# Barelang-FC_Strategy.net
KiCad netlist of a schematic drawn in Altium Designer
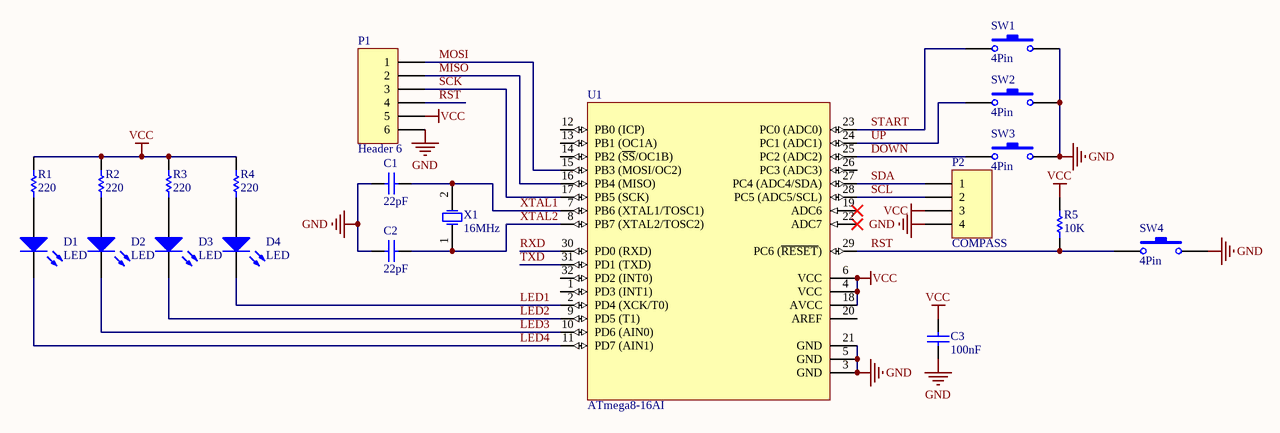
[diagram p0: Barelang-FC Strategy.SchDoc]

(export (version "E")
  (design (tool "Eeschema 10.0.6"))
  (components
    (comp (ref "C1") (value "22pF") (footprint "C0805") (libsource (lib "toko-Embedded") (part "Capacitor")))
    (comp (ref "C2") (value "22pF") (footprint "C0805") (libsource (lib "toko-Embedded") (part "Capacitor")))
    (comp (ref "C3") (value "100nF") (footprint "C0805") (libsource (lib "toko-Embedded") (part "Capacitor")))
    (comp (ref "D1") (value "LED") (footprint "CHIPLED_1206") (libsource (lib "toko-Embedded") (part "LED")))
    (comp (ref "D2") (value "LED") (footprint "CHIPLED_1206") (libsource (lib "toko-Embedded") (part "LED")))
    (comp (ref "D3") (value "LED") (footprint "CHIPLED_1206") (libsource (lib "toko-Embedded") (part "LED")))
    (comp (ref "D4") (value "LED") (footprint "CHIPLED_1206") (libsource (lib "toko-Embedded") (part "LED")))
    (comp (ref "P1")
      (value "Header 6")
      (footprint "HDR1X6")
      (description "Header, 6-Pin")
      (fields (field (name "PUBLISHER") "Altium Limited"))
      (libsource (lib "Miscellaneous Connectors") (part "Header 6"))
    )
    (comp (ref "P2")
      (value "COMPASS")
      (footprint "HDR1X4")
      (description "Header, 4-Pin")
      (fields (field (name "PUBLISHER") "Altium Limited"))
      (libsource (lib "Miscellaneous Connectors") (part "Header 4"))
    )
    (comp (ref "R1") (value "220") (footprint "R0805") (libsource (lib "toko-Embedded") (part "Resistor")))
    (comp (ref "R2") (value "220") (footprint "R0805") (libsource (lib "toko-Embedded") (part "Resistor")))
    (comp (ref "R3") (value "220") (footprint "R0805") (libsource (lib "toko-Embedded") (part "Resistor")))
    (comp (ref "R4") (value "220") (footprint "R0805") (libsource (lib "toko-Embedded") (part "Resistor")))
    (comp (ref "R5") (value "10K") (footprint "R0805") (libsource (lib "toko-Embedded") (part "Resistor")))
    (comp (ref "SW1")
      (value "4Pin")
      (footprint "TACTILE-PTH-12MM")
      (libsource (lib "toko-Embedded") (part "Switch Pushbutton"))
    )
    (comp (ref "SW2")
      (value "4Pin")
      (footprint "TACTILE-PTH-12MM")
      (libsource (lib "toko-Embedded") (part "Switch Pushbutton"))
    )
    (comp (ref "SW3")
      (value "4Pin")
      (footprint "TACTILE-PTH-12MM")
      (libsource (lib "toko-Embedded") (part "Switch Pushbutton"))
    )
    (comp (ref "SW4")
      (value "4Pin")
      (footprint "TACTILE-PTH-12MM")
      (libsource (lib "toko-Embedded") (part "Switch Pushbutton"))
    )
    (comp (ref "U1")
      (value "ATmega8-16AI")
      (footprint "32A_N")
      (description "8-Bit AVR Microcontroller with 8K Bytes of In-System Programmable Flash Memory")
      (fields (field (name "PUBLISHER") "Altium Limited"))
      (libsource (lib "Atmel Microcontroller 8-Bit AVR") (part "ATmega8-16AI"))
    )
    (comp (ref "X1") (value "16MHz") (footprint "HC49US") (libsource (lib "toko-Embedded") (part "Crystal")))
  )
  (nets
    (net (code "1") (name "/DOWN") (class "Default")
      (node (ref "SW3") (pin "1") (pinfunction "1_1") (pintype "passive"))
      (node (ref "U1") (pin "25") (pinfunction "PC2_(ADC2)_25") (pintype "bidirectional"))
    )
    (net (code "2") (name "/LED1") (class "Default")
      (node (ref "D4") (pin "2") (pinfunction "K_2") (pintype "passive"))
      (node (ref "U1") (pin "2") (pinfunction "PD4_(XCK/T0)_2") (pintype "bidirectional"))
    )
    (net (code "3") (name "/LED2") (class "Default")
      (node (ref "D3") (pin "2") (pinfunction "K_2") (pintype "passive"))
      (node (ref "U1") (pin "9") (pinfunction "PD5_(T1)_9") (pintype "bidirectional"))
    )
    (net (code "4") (name "/LED3") (class "Default")
      (node (ref "D2") (pin "2") (pinfunction "K_2") (pintype "passive"))
      (node (ref "U1") (pin "10") (pinfunction "PD6_(AIN0)_10") (pintype "bidirectional"))
    )
    (net (code "5") (name "/LED4") (class "Default")
      (node (ref "D1") (pin "2") (pinfunction "K_2") (pintype "passive"))
      (node (ref "U1") (pin "11") (pinfunction "PD7_(AIN1)_11") (pintype "bidirectional"))
    )
    (net (code "6") (name "/MISO") (class "Default")
      (node (ref "P1") (pin "2") (pinfunction "2_2") (pintype "passive"))
      (node (ref "U1") (pin "16") (pinfunction "PB4_(MISO)_16") (pintype "bidirectional"))
    )
    (net (code "7") (name "/MOSI") (class "Default")
      (node (ref "P1") (pin "1") (pinfunction "1_1") (pintype "passive"))
      (node (ref "U1") (pin "15") (pinfunction "PB3_(MOSI/OC2)_15") (pintype "bidirectional"))
    )
    (net (code "8") (name "/RST") (class "Default")
      (node (ref "P1") (pin "4") (pinfunction "4_4") (pintype "passive"))
      (node (ref "R5") (pin "1") (pinfunction "1_1") (pintype "passive"))
      (node (ref "SW4") (pin "1") (pinfunction "1_1") (pintype "passive"))
      (node (ref "U1") (pin "29") (pinfunction "PC6_(~{RESET})_29") (pintype "bidirectional"))
    )
    (net (code "9") (name "/RXD") (class "Default")
      (node (ref "U1") (pin "30") (pinfunction "PD0_(RXD)_30") (pintype "bidirectional"))
    )
    (net (code "10") (name "/SCK") (class "Default")
      (node (ref "P1") (pin "3") (pinfunction "3_3") (pintype "passive"))
      (node (ref "U1") (pin "17") (pinfunction "PB5_(SCK)_17") (pintype "bidirectional"))
    )
    (net (code "11") (name "/SCL") (class "Default")
      (node (ref "P2") (pin "2") (pinfunction "2_2") (pintype "passive"))
      (node (ref "U1") (pin "28") (pinfunction "PC5_(ADC5/SCL)_28") (pintype "bidirectional"))
    )
    (net (code "12") (name "/SDA") (class "Default")
      (node (ref "P2") (pin "1") (pinfunction "1_1") (pintype "passive"))
      (node (ref "U1") (pin "27") (pinfunction "PC4_(ADC4/SDA)_27") (pintype "bidirectional"))
    )
    (net (code "13") (name "/START") (class "Default")
      (node (ref "SW1") (pin "1") (pinfunction "1_1") (pintype "passive"))
      (node (ref "U1") (pin "23") (pinfunction "PC0_(ADC0)_23") (pintype "bidirectional"))
    )
    (net (code "14") (name "/TXD") (class "Default")
      (node (ref "U1") (pin "31") (pinfunction "PD1_(TXD)_31") (pintype "bidirectional"))
    )
    (net (code "15") (name "/UP") (class "Default")
      (node (ref "SW2") (pin "1") (pinfunction "1_1") (pintype "passive"))
      (node (ref "U1") (pin "24") (pinfunction "PC1_(ADC1)_24") (pintype "bidirectional"))
    )
    (net (code "16") (name "/XTAL1") (class "Default")
      (node (ref "C1") (pin "2") (pinfunction "2_2") (pintype "passive"))
      (node (ref "U1") (pin "7") (pinfunction "PB6_(XTAL1/TOSC1)_7") (pintype "bidirectional"))
      (node (ref "X1") (pin "2") (pinfunction "OSC2_2") (pintype "passive"))
    )
    (net (code "17") (name "/XTAL2") (class "Default")
      (node (ref "C2") (pin "2") (pinfunction "2_2") (pintype "passive"))
      (node (ref "U1") (pin "8") (pinfunction "PB7_(XTAL2/TOSC2)_8") (pintype "bidirectional"))
      (node (ref "X1") (pin "1") (pinfunction "OSC1_1") (pintype "passive"))
    )
    (net (code "18") (name "GND") (class "Default")
      (node (ref "C1") (pin "1") (pinfunction "1_1") (pintype "passive"))
      (node (ref "C2") (pin "1") (pinfunction "1_1") (pintype "passive"))
      (node (ref "C3") (pin "1") (pinfunction "1_1") (pintype "passive"))
      (node (ref "P1") (pin "6") (pinfunction "6_6") (pintype "passive"))
      (node (ref "P2") (pin "4") (pinfunction "4_4") (pintype "passive"))
      (node (ref "SW1") (pin "2") (pinfunction "2_2") (pintype "passive"))
      (node (ref "SW2") (pin "2") (pinfunction "2_2") (pintype "passive"))
      (node (ref "SW3") (pin "2") (pinfunction "2_2") (pintype "passive"))
      (node (ref "SW4") (pin "2") (pinfunction "2_2") (pintype "passive"))
      (node (ref "U1") (pin "21") (pinfunction "GND_21") (pintype "power_in"))
      (node (ref "U1") (pin "3") (pinfunction "GND_3") (pintype "power_in"))
      (node (ref "U1") (pin "5") (pinfunction "GND_5") (pintype "power_in"))
    )
    (net (code "19") (name "Net-(D1-A)") (class "Default")
      (node (ref "D1") (pin "1") (pinfunction "A_1") (pintype "passive"))
      (node (ref "R1") (pin "1") (pinfunction "1_1") (pintype "passive"))
    )
    (net (code "20") (name "Net-(D2-A)") (class "Default")
      (node (ref "D2") (pin "1") (pinfunction "A_1") (pintype "passive"))
      (node (ref "R2") (pin "1") (pinfunction "1_1") (pintype "passive"))
    )
    (net (code "21") (name "Net-(D3-A)") (class "Default")
      (node (ref "D3") (pin "1") (pinfunction "A_1") (pintype "passive"))
      (node (ref "R3") (pin "1") (pinfunction "1_1") (pintype "passive"))
    )
    (net (code "22") (name "Net-(D4-A)") (class "Default")
      (node (ref "D4") (pin "1") (pinfunction "A_1") (pintype "passive"))
      (node (ref "R4") (pin "1") (pinfunction "1_1") (pintype "passive"))
    )
    (net (code "23") (name "VCC") (class "Default")
      (node (ref "C3") (pin "2") (pinfunction "2_2") (pintype "passive"))
      (node (ref "P1") (pin "5") (pinfunction "5_5") (pintype "passive"))
      (node (ref "P2") (pin "3") (pinfunction "3_3") (pintype "passive"))
      (node (ref "R1") (pin "2") (pinfunction "2_2") (pintype "passive"))
      (node (ref "R2") (pin "2") (pinfunction "2_2") (pintype "passive"))
      (node (ref "R3") (pin "2") (pinfunction "2_2") (pintype "passive"))
      (node (ref "R4") (pin "2") (pinfunction "2_2") (pintype "passive"))
      (node (ref "R5") (pin "2") (pinfunction "2_2") (pintype "passive"))
      (node (ref "U1") (pin "18") (pinfunction "AVCC_18") (pintype "power_in"))
      (node (ref "U1") (pin "4") (pinfunction "VCC_4") (pintype "power_in"))
      (node (ref "U1") (pin "6") (pinfunction "VCC_6") (pintype "power_in"))
    )
    (net (code "24") (name "unconnected-(U1-ADC6-Pad19)") (class "Default")
      (node (ref "U1") (pin "19") (pinfunction "ADC6_19") (pintype "input+no_connect"))
    )
    (net (code "25") (name "unconnected-(U1-ADC7-Pad22)") (class "Default")
      (node (ref "U1") (pin "22") (pinfunction "ADC7_22") (pintype "input+no_connect"))
    )
    (net (code "26") (name "unconnected-(U1-AREF-Pad20)") (class "Default")
      (node (ref "U1") (pin "20") (pinfunction "AREF_20") (pintype "passive"))
    )
    (net (code "27") (name "unconnected-(U1-PB0_(ICP)-Pad12)") (class "Default")
      (node (ref "U1") (pin "12") (pinfunction "PB0_(ICP)_12") (pintype "bidirectional"))
    )
    (net (code "28") (name "unconnected-(U1-PB1_(OC1A)-Pad13)") (class "Default")
      (node (ref "U1") (pin "13") (pinfunction "PB1_(OC1A)_13") (pintype "bidirectional"))
    )
    (net (code "29") (name "unconnected-(U1-PB2_(~{SS}{slash}OC1B)-Pad14)") (class "Default")
      (node (ref "U1") (pin "14") (pinfunction "PB2_(~{SS}/OC1B)_14") (pintype "bidirectional"))
    )
    (net (code "30") (name "unconnected-(U1-PC3_(ADC3)-Pad26)") (class "Default")
      (node (ref "U1") (pin "26") (pinfunction "PC3_(ADC3)_26") (pintype "bidirectional"))
    )
    (net (code "31") (name "unconnected-(U1-PD2_(INT0)-Pad32)") (class "Default")
      (node (ref "U1") (pin "32") (pinfunction "PD2_(INT0)_32") (pintype "bidirectional"))
    )
    (net (code "32") (name "unconnected-(U1-PD3_(INT1)-Pad1)") (class "Default")
      (node (ref "U1") (pin "1") (pinfunction "PD3_(INT1)_1") (pintype "bidirectional"))
    )
  )
)
